# Charger_Interface_-_J1772_Interface.net
KiCad netlist of a schematic drawn in Altium Designer
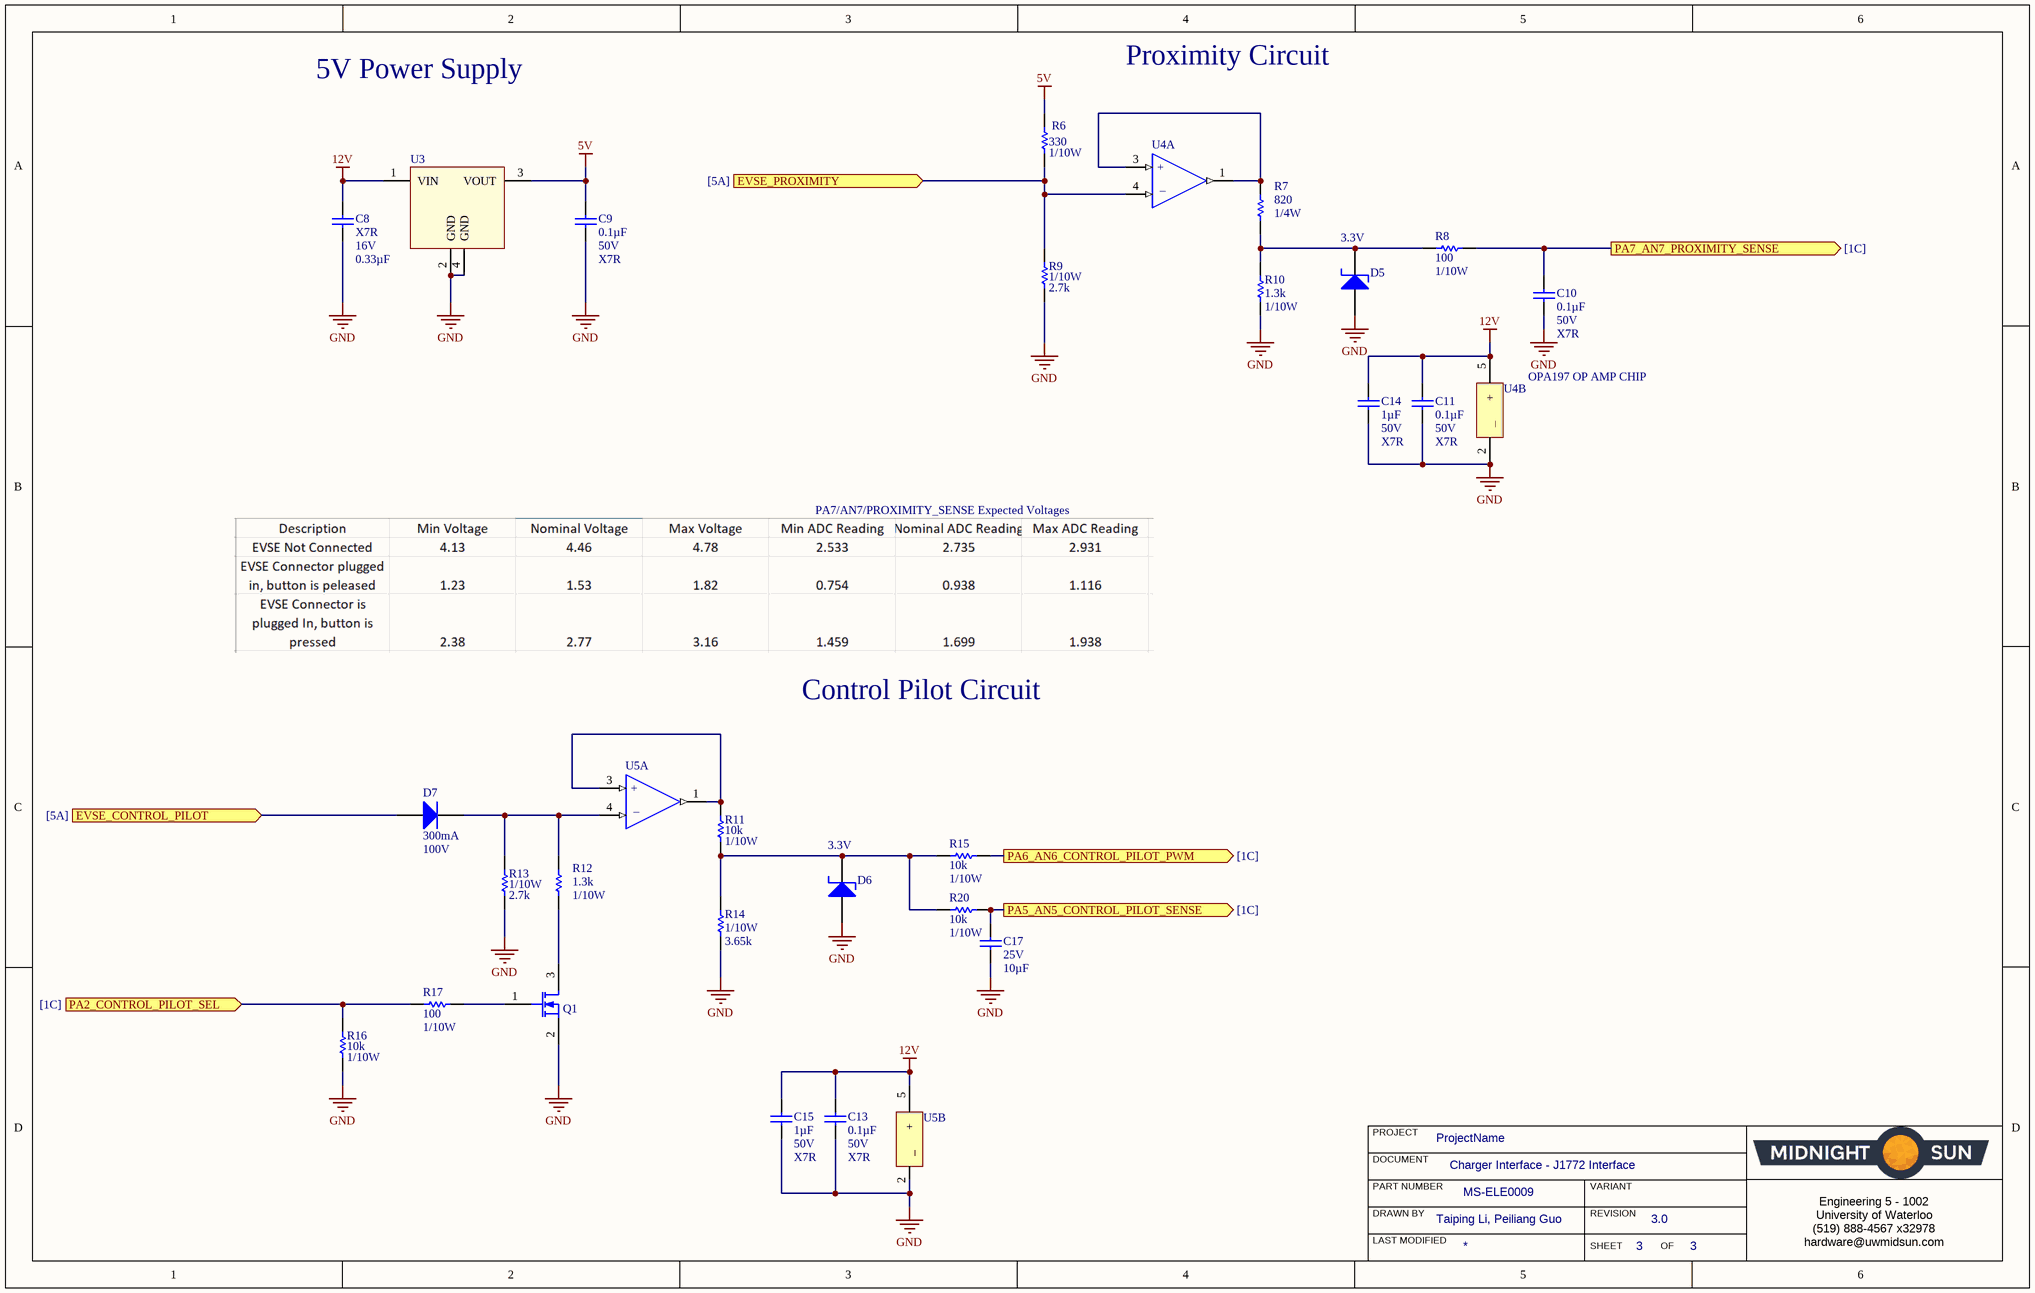
[diagram p0: Charger Interface - J1772 Interface.SchDoc]

(export (version "E")
  (design (tool "Eeschema 10.0.6"))
  (components
    (comp (ref "C8")
      (value "CAP CER 0.33UF 16V 10% X7R 0603")
      (footprint "CAP, 0603")
      (description "0.33µF ±10% 16V Ceramic Capacitor X7R 0603 (1608 Metric)")
      (fields
        (field (name "MANUFACTURER") "KEMET")
        (field (name "MANUFACTURER PART NUMBER") "C0603C334K4RACTU")
        (field (name "DIELECTRIC") "X7R")
        (field (name "VOLTAGE") "16V")
        (field (name "CAPACITANCE") "0.33µF")
      )
      (libsource (lib "Schematic Diagrams") (part "CAP CER 0.33UF 16V 10% X7R 0603"))
    )
    (comp (ref "C9")
      (value "CAP CER 0.1UF 50V 10% X7R 0603")
      (footprint "CAP, 0603")
      (description "0.10µF ±10% 50V Ceramic Capacitor X7R 0603 (1608 Metric)")
      (fields
        (field (name "TOLERANCE") "±10%")
        (field (name "CAPACITANCE") "0.1µF")
        (field (name "VOLTAGE") "50V")
        (field (name "TEMPERATURE COEFFICIENT") "X7R")
      )
      (libsource (lib "Schematic Diagrams") (part "CAP CER 0.1UF 50V 10% X7R 0603"))
    )
    (comp (ref "C10")
      (value "CAP CER 0.1UF 50V 10% X7R 0603")
      (footprint "CAP, 0603")
      (description "0.10µF ±10% 50V Ceramic Capacitor X7R 0603 (1608 Metric)")
      (fields
        (field (name "TOLERANCE") "±10%")
        (field (name "CAPACITANCE") "0.1µF")
        (field (name "VOLTAGE") "50V")
        (field (name "TEMPERATURE COEFFICIENT") "X7R")
      )
      (libsource (lib "Schematic Diagrams") (part "CAP CER 0.1UF 50V 10% X7R 0603"))
    )
    (comp (ref "C11")
      (value "CAP CER 0.1UF 50V 10% X7R 0603")
      (footprint "CAP, 0603")
      (description "0.10µF ±10% 50V Ceramic Capacitor X7R 0603 (1608 Metric)")
      (fields
        (field (name "TOLERANCE") "±10%")
        (field (name "CAPACITANCE") "0.1µF")
        (field (name "VOLTAGE") "50V")
        (field (name "TEMPERATURE COEFFICIENT") "X7R")
      )
      (libsource (lib "Schematic Diagrams") (part "CAP CER 0.1UF 50V 10% X7R 0603"))
    )
    (comp (ref "C13")
      (value "CAP CER 0.1UF 50V 10% X7R 0603")
      (footprint "CAP, 0603")
      (description "0.10µF ±10% 50V Ceramic Capacitor X7R 0603 (1608 Metric)")
      (fields
        (field (name "TOLERANCE") "±10%")
        (field (name "CAPACITANCE") "0.1µF")
        (field (name "VOLTAGE") "50V")
        (field (name "TEMPERATURE COEFFICIENT") "X7R")
      )
      (libsource (lib "Schematic Diagrams") (part "CAP CER 0.1UF 50V 10% X7R 0603"))
    )
    (comp (ref "C14")
      (value "CAP CER 1UF 50V 10% X7R 0603")
      (footprint "CAP, 0603")
      (description "1µF ±10% 50V Ceramic Capacitor X7R 0603 (1608 Metric)")
      (fields
        (field (name "TOLERANCE") "±10%")
        (field (name "CAPACITANCE") "1µF")
        (field (name "VOLTAGE") "50V")
        (field (name "TEMPERATURE COEFFICIENT") "X7R")
      )
      (libsource (lib "Schematic Diagrams") (part "CAP CER 1UF 50V 10% X7R 0603"))
    )
    (comp (ref "C15")
      (value "CAP CER 1UF 50V 10% X7R 0603")
      (footprint "CAP, 0603")
      (description "1µF ±10% 50V Ceramic Capacitor X7R 0603 (1608 Metric)")
      (fields
        (field (name "TOLERANCE") "±10%")
        (field (name "CAPACITANCE") "1µF")
        (field (name "VOLTAGE") "50V")
        (field (name "TEMPERATURE COEFFICIENT") "X7R")
      )
      (libsource (lib "Schematic Diagrams") (part "CAP CER 1UF 50V 10% X7R 0603"))
    )
    (comp (ref "C17")
      (value "CAP CER 10uF 25V 10% X5R 0805")
      (footprint "CAP, 0805")
      (description "10µF ±10% 25V Ceramic Capacitor X5R 0805 (2012 Metric)")
      (fields
        (field (name "MANUFACTURER") "Murata Electronics North America")
        (field (name "MANUFACTURER PART NUMBER") "GRM21BR61E106KA73L")
        (field (name "VOLTAGE - RATED") "25V")
        (field (name "CAPACITANCE") "10µF")
      )
      (libsource (lib "Schematic Diagrams") (part "CAP CER 10uF 25V 10% X5R 0805"))
    )
    (comp (ref "D5")
      (value "DIODE ZENER 3.3V 200MW SOD323")
      (footprint "sod-323")
      (description "Zener Diode 3.3V 200mW ±5% Surface Mount SOD-323")
      (fields (field (name "VOLTAGE") "3.3V") (field (name "SOURCE") "Schematic Diagrams.SchLib"))
      (libsource (lib "University of Waterloo - Solar Car Team") (part "Symbol"))
    )
    (comp (ref "D6")
      (value "DIODE ZENER 3.3V 200MW SOD323")
      (footprint "sod-323")
      (description "Zener Diode 3.3V 200mW ±5% Surface Mount SOD-323")
      (fields (field (name "VOLTAGE") "3.3V") (field (name "SOURCE") "Schematic Diagrams.SchLib"))
      (libsource (lib "University of Waterloo - Solar Car Team") (part "Symbol"))
    )
    (comp (ref "D7")
      (value "DIODE GEN PURP 100V 300MA SOD123")
      (footprint "DIODE GEN PURP 100V 300MA SOD123")
      (description "Diode Standard 100V 300mA (DC) Surface Mount SOD-123")
      (fields
        (field (name "MANUFACTURER") "Diodes Zetex")
        (field (name "MANUFACTURER PART NUMBER") "1N4148WQ-7-F")
        (field (name "FORWARD CURRENT") "300mA")
        (field (name "MAX REPETITIVE REVERSE VOLTAGE (VRRM)") "100V")
      )
      (libsource (lib "Schematic Diagrams") (part "DIODE GEN PURP 100V 300MA SOD123"))
    )
    (comp (ref "Q1")
      (value "MOSFET N-CH 30V 6.2A 0.9W SOT-23")
      (footprint "MOSFET N-CH 30V 6.2A 0.9W SOT-23")
      (description "N-Channel 30V 6.2A (Ta) 900mW (Ta) Surface Mount SOT-23")
      (fields (field (name "MANUFACTURER") "Diodes") (field (name "MANUFACTURER PART NUMBER") "DMN3023L-7"))
      (libsource (lib "Schematic Diagrams") (part "MOSFET N-CH 30V 6.2A 0.9W SOT-23"))
    )
    (comp (ref "R6")
      (value "RES 330 OHM 1% 1/10W 0603")
      (footprint "RES, 0603")
      (fields
        (field (name "MANUFACTURER") "TE Connectivity")
        (field (name "MANUFACTURER PART NUMBER") "1-2176339-9")
        (field (name "RESISTANCE") "330")
        (field (name "POWER") "1/10W")
      )
      (libsource (lib "Schematic Diagrams") (part "RES 330 OHM 1% 1/10W 0603"))
    )
    (comp (ref "R7")
      (value "RES 820 OHM 5% 1/4W 0603")
      (footprint "RES, 0603")
      (description "RES SMD 820 OHM 5% 1/4W 0603")
      (fields
        (field (name "TOLERANCE") "±5%")
        (field (name "RESISTANCE") "820")
        (field (name "POWER") "1/4W")
      )
      (libsource (lib "Schematic Diagrams") (part "RES 820 OHM 5% 1/4W 0603"))
    )
    (comp (ref "R8")
      (value "RES 100 OHM 1% 1/10W 0603")
      (footprint "RES, 0603")
      (description "100 Ohm ±1% 0.1W, 1/10W Chip Resistor 0603 (1608 Metric) Moisture Resistant Thick Film")
      (fields
        (field (name "TOLERANCE") "±1%")
        (field (name "RESISTANCE") "100")
        (field (name "POWER") "1/10W")
      )
      (libsource (lib "Schematic Diagrams") (part "RES 100 OHM 1% 1/10W 0603"))
    )
    (comp (ref "R9")
      (value "RES 2.7K OHM 1% 1/10W 0603")
      (footprint "RES, 0603")
      (fields
        (field (name "MANUFACTURER") "TE Connectivity")
        (field (name "MANUFACTURER PART NUMBER") "3-2176339-0")
        (field (name "POWER") "1/10W")
        (field (name "RESISTANCE") "2.7k")
      )
      (libsource (lib "Schematic Diagrams") (part "RES 2.7K OHM 1% 1/10W 0603"))
    )
    (comp (ref "R10")
      (value "RES 1.3K OHM 1% 1/10W 0603")
      (footprint "RES, 0603")
      (description "1.3 kOhms ±1% 0.1W, 1/10W Chip Resistor 0603 (1608 Metric) Moisture Resistant Thick Film")
      (fields
        (field (name "MANUFACTURER") "Yageo")
        (field (name "MANUFACTURER PART NUMBER") "RC0603FR-071K3L")
        (field (name "RESISTANCE") "1.3k")
        (field (name "POWER RATING") "1/10W")
      )
      (libsource (lib "Schematic Diagrams") (part "RES 1.3K OHM 1% 1/10W 0603"))
    )
    (comp (ref "R11")
      (value "RES 10K OHM 1% 1/10W 0603")
      (footprint "RES, 0603")
      (description "RES SMD 10K OHM 1% 1/10W 0603")
      (fields
        (field (name "TOLERANCE") "±1%")
        (field (name "RESISTANCE") "10k")
        (field (name "POWER") "1/10W")
      )
      (libsource (lib "Schematic Diagrams") (part "RES 10K OHM 1% 1/10W 0603"))
    )
    (comp (ref "R12")
      (value "RES 1.3K OHM 1% 1/10W 0603")
      (footprint "RES, 0603")
      (description "1.3 kOhms ±1% 0.1W, 1/10W Chip Resistor 0603 (1608 Metric) Moisture Resistant Thick Film")
      (fields
        (field (name "MANUFACTURER") "Yageo")
        (field (name "MANUFACTURER PART NUMBER") "RC0603FR-071K3L")
        (field (name "RESISTANCE") "1.3k")
        (field (name "POWER RATING") "1/10W")
      )
      (libsource (lib "Schematic Diagrams") (part "RES 1.3K OHM 1% 1/10W 0603"))
    )
    (comp (ref "R13")
      (value "RES 2.7K OHM 1% 1/10W 0603")
      (footprint "RES, 0603")
      (fields
        (field (name "MANUFACTURER") "TE Connectivity")
        (field (name "MANUFACTURER PART NUMBER") "3-2176339-0")
        (field (name "POWER") "1/10W")
        (field (name "RESISTANCE") "2.7k")
      )
      (libsource (lib "Schematic Diagrams") (part "RES 2.7K OHM 1% 1/10W 0603"))
    )
    (comp (ref "R14")
      (value "RES 3.65K OHM 0.1% 1/10W 0603")
      (footprint "RES, 0603")
      (description "3.65 kOhms ±0.1% 0.1W, 1/10W Chip Resistor 0603 (1608 Metric) Automotive AEC-Q200 Thin Film")
      (fields
        (field (name "MANUFACTURER") "Panasonic")
        (field (name "MANUFACTURER PART NUMBER") "ERA3AEB3651V")
        (field (name "POWER RATING") "1/10W")
        (field (name "RESISTANCE") "3.65k")
      )
      (libsource (lib "Schematic Diagrams") (part "RES 3.65K OHM 0.1% 1/10W 0603"))
    )
    (comp (ref "R15")
      (value "RES 10K OHM 1% 1/10W 0603")
      (footprint "RES, 0603")
      (description "RES SMD 10K OHM 1% 1/10W 0603")
      (fields
        (field (name "TOLERANCE") "±1%")
        (field (name "RESISTANCE") "10k")
        (field (name "POWER") "1/10W")
      )
      (libsource (lib "Schematic Diagrams") (part "RES 10K OHM 1% 1/10W 0603"))
    )
    (comp (ref "R16")
      (value "RES 10K OHM 1% 1/10W 0603")
      (footprint "RES, 0603")
      (description "RES SMD 10K OHM 1% 1/10W 0603")
      (fields
        (field (name "TOLERANCE") "±1%")
        (field (name "RESISTANCE") "10k")
        (field (name "POWER") "1/10W")
      )
      (libsource (lib "Schematic Diagrams") (part "RES 10K OHM 1% 1/10W 0603"))
    )
    (comp (ref "R17")
      (value "RES 100 OHM 1% 1/10W 0603")
      (footprint "RES, 0603")
      (description "100 Ohm ±1% 0.1W, 1/10W Chip Resistor 0603 (1608 Metric) Moisture Resistant Thick Film")
      (fields
        (field (name "TOLERANCE") "±1%")
        (field (name "RESISTANCE") "100")
        (field (name "POWER") "1/10W")
      )
      (libsource (lib "Schematic Diagrams") (part "RES 100 OHM 1% 1/10W 0603"))
    )
    (comp (ref "R20")
      (value "RES 10K OHM 1% 1/10W 0603")
      (footprint "RES, 0603")
      (description "RES SMD 10K OHM 1% 1/10W 0603")
      (fields
        (field (name "TOLERANCE") "±1%")
        (field (name "RESISTANCE") "10k")
        (field (name "POWER") "1/10W")
      )
      (libsource (lib "Schematic Diagrams") (part "RES 10K OHM 1% 1/10W 0603"))
    )
    (comp (ref "U3")
      (value "IC REG LDO 5V 0.5A SOT223")
      (footprint "SOT223_N")
      (description "Linear Voltage Regulator IC Positive Fixed Output 5V 500mA SOT-223-4")
      (libsource (lib "Schematic Diagrams") (part "IC REG LDO 5V 0.5A SOT223"))
    )
    (comp (ref "U4")
      (value "IC OP AMP GP 1 CIRCUIT SOT23-5")
      (footprint "IC OP AMP GP RR 10MHZ SOT-23-5")
      (description "General Purpose Amplifier 1 Circuit Rail-to-Rail SOT-23-5")
      (fields
        (field (name "MANUFACTURER") "Texas Instruments")
        (field (name "MANUFACTURER PART NUMBER") "OPA2197IDGKR")
        (field (name "SOURCE") "Schematic Diagrams.SchLib")
      )
      (libsource (lib "University of Waterloo - Solar Car Team") (part "IC OP AMP GP 1 CIRCUIT SOT23-5"))
    )
    (comp (ref "U5")
      (value "IC OP AMP GP 1 CIRCUIT SOT23-5")
      (footprint "IC OP AMP GP RR 10MHZ SOT-23-5")
      (description "General Purpose Amplifier 1 Circuit Rail-to-Rail SOT-23-5")
      (fields
        (field (name "MANUFACTURER") "Texas Instruments")
        (field (name "MANUFACTURER PART NUMBER") "OPA2197IDGKR")
        (field (name "SOURCE") "Schematic Diagrams.SchLib")
      )
      (libsource (lib "University of Waterloo - Solar Car Team") (part "IC OP AMP GP 1 CIRCUIT SOT23-5"))
    )
  )
  (nets
    (net (code "1") (name "/EVSE_CONTROL_PILOT") (class "Default")
      (node (ref "D7") (pin "1") (pinfunction "A_1") (pintype "passive"))
    )
    (net (code "2") (name "/EVSE_PROXIMITY") (class "Default")
      (node (ref "R6") (pin "2") (pinfunction "2_2") (pintype "passive"))
      (node (ref "R9") (pin "1") (pinfunction "1_1") (pintype "passive"))
      (node (ref "U4") (pin "4") (pinfunction "-IN_A_4") (pintype "input"))
    )
    (net (code "3") (name "/PA2_CONTROL_PILOT_SEL") (class "Default")
      (node (ref "R16") (pin "1") (pinfunction "1_1") (pintype "passive"))
      (node (ref "R17") (pin "1") (pinfunction "1_1") (pintype "passive"))
    )
    (net (code "4") (name "/PA5_AN5_CONTROL_PILOT_SENSE") (class "Default")
      (node (ref "C17") (pin "1") (pinfunction "1_1") (pintype "passive"))
      (node (ref "R20") (pin "2") (pinfunction "2_2") (pintype "passive"))
    )
    (net (code "5") (name "/PA6_AN6_CONTROL_PILOT_PWM") (class "Default")
      (node (ref "R15") (pin "2") (pinfunction "2_2") (pintype "passive"))
    )
    (net (code "6") (name "/PA7_AN7_PROXIMITY_SENSE") (class "Default")
      (node (ref "C10") (pin "1") (pinfunction "1_1") (pintype "passive"))
      (node (ref "R8") (pin "2") (pinfunction "2_2") (pintype "passive"))
    )
    (net (code "7") (name "5V") (class "Default")
      (node (ref "C9") (pin "1") (pinfunction "1_1") (pintype "passive"))
      (node (ref "R6") (pin "1") (pinfunction "1_1") (pintype "passive"))
      (node (ref "U3") (pin "3") (pinfunction "VOUT_3") (pintype "power_in"))
    )
    (net (code "8") (name "12V") (class "Default")
      (node (ref "C11") (pin "1") (pinfunction "1_1") (pintype "passive"))
      (node (ref "C13") (pin "1") (pinfunction "1_1") (pintype "passive"))
      (node (ref "C14") (pin "1") (pinfunction "1_1") (pintype "passive"))
      (node (ref "C15") (pin "1") (pinfunction "1_1") (pintype "passive"))
      (node (ref "C8") (pin "1") (pinfunction "1_1") (pintype "passive"))
      (node (ref "U3") (pin "1") (pinfunction "VIN_1") (pintype "power_in"))
      (node (ref "U4") (pin "5") (pinfunction "+_5") (pintype "power_in"))
      (node (ref "U5") (pin "5") (pinfunction "+_5") (pintype "power_in"))
    )
    (net (code "9") (name "GND") (class "Default")
      (node (ref "C10") (pin "2") (pinfunction "2_2") (pintype "passive"))
      (node (ref "C11") (pin "2") (pinfunction "2_2") (pintype "passive"))
      (node (ref "C13") (pin "2") (pinfunction "2_2") (pintype "passive"))
      (node (ref "C14") (pin "2") (pinfunction "2_2") (pintype "passive"))
      (node (ref "C15") (pin "2") (pinfunction "2_2") (pintype "passive"))
      (node (ref "C17") (pin "2") (pinfunction "2_2") (pintype "passive"))
      (node (ref "C8") (pin "2") (pinfunction "2_2") (pintype "passive"))
      (node (ref "C9") (pin "2") (pinfunction "2_2") (pintype "passive"))
      (node (ref "D5") (pin "1") (pinfunction "A_1") (pintype "passive"))
      (node (ref "D6") (pin "1") (pinfunction "A_1") (pintype "passive"))
      (node (ref "Q1") (pin "2") (pinfunction "S_2") (pintype "passive"))
      (node (ref "R10") (pin "2") (pinfunction "2_2") (pintype "passive"))
      (node (ref "R13") (pin "2") (pinfunction "2_2") (pintype "passive"))
      (node (ref "R14") (pin "2") (pinfunction "2_2") (pintype "passive"))
      (node (ref "R16") (pin "2") (pinfunction "2_2") (pintype "passive"))
      (node (ref "R9") (pin "2") (pinfunction "2_2") (pintype "passive"))
      (node (ref "U3") (pin "2") (pinfunction "GND_2") (pintype "power_in"))
      (node (ref "U3") (pin "4") (pinfunction "GND_4") (pintype "power_in"))
      (node (ref "U4") (pin "2") (pinfunction "__2") (pintype "power_in"))
      (node (ref "U5") (pin "2") (pinfunction "__2") (pintype "power_in"))
    )
    (net (code "10") (name "Net-(D5-K)") (class "Default")
      (node (ref "D5") (pin "2") (pinfunction "K_2") (pintype "passive"))
      (node (ref "R10") (pin "1") (pinfunction "1_1") (pintype "passive"))
      (node (ref "R7") (pin "2") (pinfunction "2_2") (pintype "passive"))
      (node (ref "R8") (pin "1") (pinfunction "1_1") (pintype "passive"))
    )
    (net (code "11") (name "Net-(D6-K)") (class "Default")
      (node (ref "D6") (pin "2") (pinfunction "K_2") (pintype "passive"))
      (node (ref "R11") (pin "2") (pinfunction "2_2") (pintype "passive"))
      (node (ref "R14") (pin "1") (pinfunction "1_1") (pintype "passive"))
      (node (ref "R15") (pin "1") (pinfunction "1_1") (pintype "passive"))
      (node (ref "R20") (pin "1") (pinfunction "1_1") (pintype "passive"))
    )
    (net (code "12") (name "Net-(D7-K)") (class "Default")
      (node (ref "D7") (pin "2") (pinfunction "K_2") (pintype "passive"))
      (node (ref "R12") (pin "1") (pinfunction "1_1") (pintype "passive"))
      (node (ref "R13") (pin "1") (pinfunction "1_1") (pintype "passive"))
      (node (ref "U5") (pin "4") (pinfunction "-IN_A_4") (pintype "input"))
    )
    (net (code "13") (name "Net-(Q1-D)") (class "Default")
      (node (ref "Q1") (pin "3") (pinfunction "D_3") (pintype "passive"))
      (node (ref "R12") (pin "2") (pinfunction "2_2") (pintype "passive"))
    )
    (net (code "14") (name "Net-(Q1-G)") (class "Default")
      (node (ref "Q1") (pin "1") (pinfunction "G_1") (pintype "passive"))
      (node (ref "R17") (pin "2") (pinfunction "2_2") (pintype "passive"))
    )
    (net (code "15") (name "Net-(U4A-+IN_A)") (class "Default")
      (node (ref "R7") (pin "1") (pinfunction "1_1") (pintype "passive"))
      (node (ref "U4") (pin "1") (pinfunction "OUT_A_1") (pintype "output"))
      (node (ref "U4") (pin "3") (pinfunction "+IN_A_3") (pintype "input"))
    )
    (net (code "16") (name "Net-(U5A-+IN_A)") (class "Default")
      (node (ref "R11") (pin "1") (pinfunction "1_1") (pintype "passive"))
      (node (ref "U5") (pin "1") (pinfunction "OUT_A_1") (pintype "output"))
      (node (ref "U5") (pin "3") (pinfunction "+IN_A_3") (pintype "input"))
    )
  )
)
